# dsp.net
KiCad netlist of a schematic drawn in Altium Designer
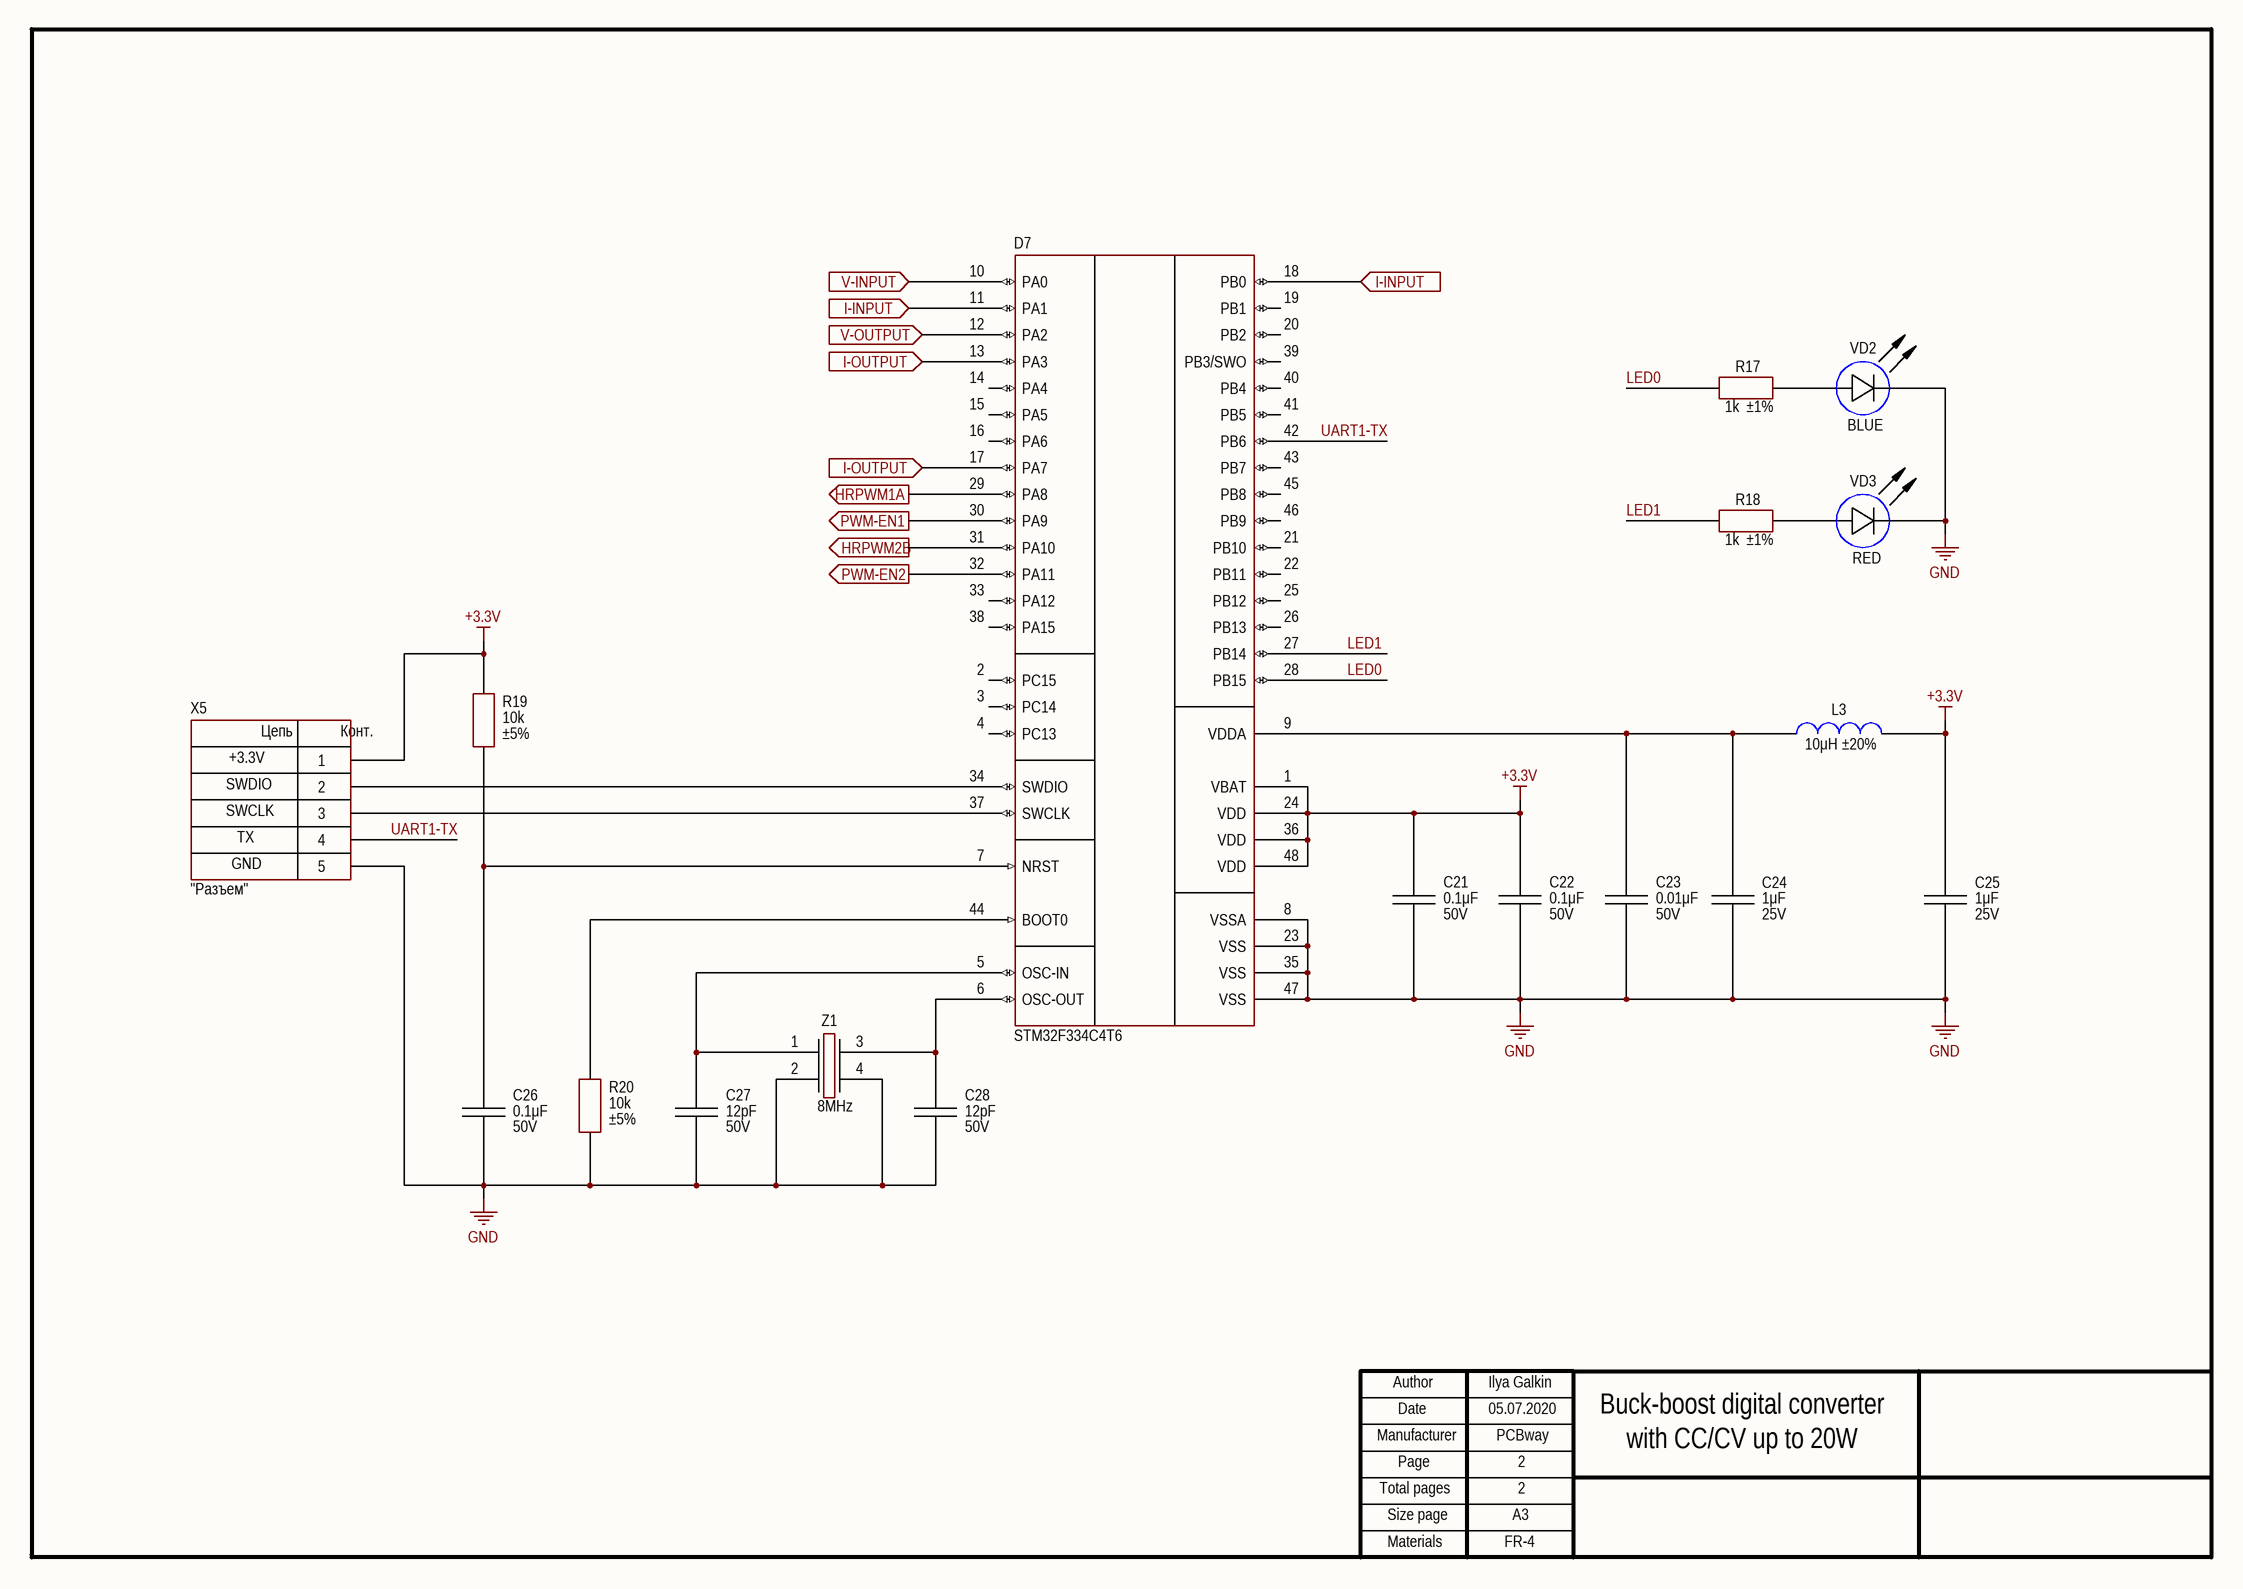
[diagram p0: dsp.SchDoc]

(export (version "E")
  (design (tool "Eeschema 10.0.6"))
  (components
    (comp (ref "C21")
      (value "0.1μF")
      (footprint "CAP: 0603")
      (fields
        (field (name "MANUFACTURER") "Yageo")
        (field (name "PARTNUMBER") "CL10B104KB8WPND")
        (field (name "VALUEMANUFACTURERPARTNUMBER") "Ceramic capacitor, 0.1μF, X7R, ±10%, 50V, 0603, -55...+125°C")
        (field (name "VOLTAGE") "50V")
      )
      (libsource (lib "Capacitor") (part "Ceramic_0603"))
    )
    (comp (ref "C22")
      (value "0.1μF")
      (footprint "CAP: 0603")
      (fields
        (field (name "MANUFACTURER") "Yageo")
        (field (name "PARTNUMBER") "CL10B104KB8WPND")
        (field (name "VALUEMANUFACTURERPARTNUMBER") "Ceramic capacitor, 0.1μF, X7R, ±10%, 50V, 0603, -55...+125°C")
        (field (name "VOLTAGE") "50V")
      )
      (libsource (lib "Capacitor") (part "Ceramic_0603"))
    )
    (comp (ref "C23")
      (value "0.01μF")
      (footprint "CAP: 0603")
      (fields
        (field (name "MANUFACTURER") "Yageo")
        (field (name "PARTNUMBER") "CL10B103KB8NNNC")
        (field (name "VALUEMANUFACTURERPARTNUMBER") "Ceramic capacitor, 0.01μF, X7R, ±10%, 50V, 0603, -55...+125°C")
        (field (name "VOLTAGE") "50V")
      )
      (libsource (lib "Capacitor") (part "Ceramic_0603"))
    )
    (comp (ref "C24")
      (value "1μF")
      (footprint "CAP: 0603")
      (fields
        (field (name "MANUFACTURER") "Samsung")
        (field (name "PARTNUMBER") "CL10B105KA8NNNC")
        (field (name "VALUEMANUFACTURERPARTNUMBER") "Ceramic capacitor, 1μF, X7R, ±10%, 25V, 0603, -55...+125°C")
        (field (name "VOLTAGE") "25V")
      )
      (libsource (lib "Capacitor") (part "Ceramic_0603"))
    )
    (comp (ref "C25")
      (value "1μF")
      (footprint "CAP: 0603")
      (fields
        (field (name "MANUFACTURER") "Samsung")
        (field (name "PARTNUMBER") "CL10B105KA8NNNC")
        (field (name "VALUEMANUFACTURERPARTNUMBER") "Ceramic capacitor, 1μF, X7R, ±10%, 25V, 0603, -55...+125°C")
        (field (name "VOLTAGE") "25V")
      )
      (libsource (lib "Capacitor") (part "Ceramic_0603"))
    )
    (comp (ref "C26")
      (value "0.1μF")
      (footprint "CAP: 0603")
      (fields
        (field (name "MANUFACTURER") "Yageo")
        (field (name "PARTNUMBER") "CL10B104KB8WPND")
        (field (name "VALUEMANUFACTURERPARTNUMBER") "Ceramic capacitor, 0.1μF, X7R, ±10%, 50V, 0603, -55...+125°C")
        (field (name "VOLTAGE") "50V")
      )
      (libsource (lib "Capacitor") (part "Ceramic_0603"))
    )
    (comp (ref "C27")
      (value "12pF")
      (footprint "CAP: 0603")
      (fields
        (field (name "MANUFACTURER") "Samsung")
        (field (name "PARTNUMBER") "CL10C120JB8NNNC")
        (field (name "VALUEMANUFACTURERPARTNUMBER") "Ceramic capacitor, 12pF, NPO, ±10%, 50V, 0603, -55...+125°C")
        (field (name "VOLTAGE") "50V")
      )
      (libsource (lib "Capacitor") (part "Ceramic_0603"))
    )
    (comp (ref "C28")
      (value "12pF")
      (footprint "CAP: 0603")
      (fields
        (field (name "MANUFACTURER") "Samsung")
        (field (name "PARTNUMBER") "CL10C120JB8NNNC")
        (field (name "VALUEMANUFACTURERPARTNUMBER") "Ceramic capacitor, 12pF, NPO, ±10%, 50V, 0603, -55...+125°C")
        (field (name "VOLTAGE") "50V")
      )
      (libsource (lib "Capacitor") (part "Ceramic_0603"))
    )
    (comp (ref "D7")
      (value "~")
      (footprint "48-LQFP")
      (description "Cortex-M4")
      (fields
        (field (name "MANUFACTURER") "STMicroelectronics")
        (field (name "VALUEMANUFACTURERPARTNUMBER") "IC microcontroller, 32-Bit, Cortex-M4, 72MHz, 16KB, 12KB, 2...3.6V, -40...+85°C, 48-LQFP")
        (field (name "PARTNUMBER") "STM32F334C4T6")
      )
      (libsource (lib "IC. MCU") (part "STM32F334C4T6"))
    )
    (comp (ref "L3")
      (value "10μH")
      (footprint "IND: 0603")
      (fields
        (field (name "MANUFACTURER") "Murata Electronics")
        (field (name "PARTNUMBER") "LQM18FN100M00D")
        (field (name "VALUEMANUFACTURERPARTNUMBER") "Fixed inductor, 10μH, ±20%, 0603, 50mA, -55...+125°C")
        (field (name "TOLERANCE") "±20%")
      )
      (libsource (lib "Inductor") (part "Inductor_0603"))
    )
    (comp (ref "R17")
      (value "1k")
      (footprint "RES: 0603")
      (fields
        (field (name "MANUFACTURER") "Yageo")
        (field (name "PARTNUMBER") "RC0603FR-071KL")
        (field (name "VALUEMANUFACTURERPARTNUMBER") "Resistor film, 1k, ±1%, 0603, 0.1W, -55...+125°C")
        (field (name "TOLERANCE") "±1%")
      )
      (libsource (lib "Resistor") (part "Resistor_0603"))
    )
    (comp (ref "R18")
      (value "1k")
      (footprint "RES: 0603")
      (fields
        (field (name "MANUFACTURER") "Yageo")
        (field (name "PARTNUMBER") "RC0603FR-071KL")
        (field (name "VALUEMANUFACTURERPARTNUMBER") "Resistor film, 1k, ±1%, 0603, 0.1W, -55...+125°C")
        (field (name "TOLERANCE") "±1%")
      )
      (libsource (lib "Resistor") (part "Resistor_0603"))
    )
    (comp (ref "R19")
      (value "10k")
      (footprint "RES: 0603")
      (fields
        (field (name "MANUFACTURER") "Yageo")
        (field (name "PARTNUMBER") "RC0603JR-0710KL")
        (field (name "VALUEMANUFACTURERPARTNUMBER") "Resistor film, 10k, ±5%, 0603, 0.1W, -55...+125°C")
        (field (name "TOLERANCE") "±5%")
      )
      (libsource (lib "") (part "Resistor_0603_1"))
    )
    (comp (ref "R20")
      (value "10k")
      (footprint "RES: 0603")
      (fields
        (field (name "MANUFACTURER") "Yageo")
        (field (name "PARTNUMBER") "RC0603JR-0710KL")
        (field (name "VALUEMANUFACTURERPARTNUMBER") "Resistor film, 10k, ±5%, 0603, 0.1W, -55...+125°C")
        (field (name "TOLERANCE") "±5%")
      )
      (libsource (lib "") (part "Resistor_0603_1"))
    )
    (comp (ref "VD2")
      (value "~")
      (footprint "LED: 0603B")
      (fields
        (field (name "MANUFACTURER") "Wurth")
        (field (name "VALUEMANUFACTURERPARTNUMBER") "LED, 20mA, 3.2V, 0603, -55...+150°C")
        (field (name "PARTNUMBER") "150060BS75000")
        (field (name "COLOR") "BLUE")
      )
      (libsource (lib "Diode") (part "LED_single"))
    )
    (comp (ref "VD3")
      (value "~")
      (footprint "LED: 0603R")
      (fields
        (field (name "MANUFACTURER") "Wurth")
        (field (name "VALUEMANUFACTURERPARTNUMBER") "LED, 20 mA, 2V, 0603, -55...+150°C")
        (field (name "PARTNUMBER") "150060RS75000")
        (field (name "COLOR") "RED")
      )
      (libsource (lib "Diode") (part "LED_single"))
    )
    (comp (ref "X5")
      (value "~")
      (footprint "CON: SM05B-GHS")
      (fields
        (field (name "MANUFACTURER") "JST")
        (field (name "VALUEMANUFACTURERPARTNUMBER") "Connector, 5pin, 1.25mm, 50VDC, 1A")
        (field (name "PARTNUMBER") "SM05B-GHS")
        (field (name "COMMENTTEXT") "\"Разъем\"")
      )
      (libsource (lib "Connector") (part "Connector_SM05B"))
    )
    (comp (ref "Z1")
      (value "~")
      (footprint "OSC: 3225")
      (fields
        (field (name "MANUFACTURER") "ECS")
        (field (name "PARTNUMBER") "ECS-80-12-33-JGN-TR")
        (field (name "VALUEMANUFACTURERPARTNUMBER") "Crystal, 8MHz, 12pF, ±30ppm, case 3225, -40...+85°C")
        (field (name "FREQUENCY") "8MHz")
      )
      (libsource (lib "Oscilator") (part "Crystal_3225"))
    )
  )
  (nets
    (net (code "1") (name "+3.3V") (class "Default")
      (node (ref "C21") (pin "2") (pinfunction "2_2") (pintype "power_in"))
      (node (ref "C22") (pin "2") (pinfunction "2_2") (pintype "power_in"))
      (node (ref "C25") (pin "2") (pinfunction "2_2") (pintype "power_in"))
      (node (ref "D7") (pin "1") (pinfunction "VBAT_1") (pintype "passive"))
      (node (ref "D7") (pin "24") (pinfunction "VDD_24") (pintype "passive"))
      (node (ref "D7") (pin "36") (pinfunction "VDD_36") (pintype "passive"))
      (node (ref "D7") (pin "48") (pinfunction "VDD_48") (pintype "passive"))
      (node (ref "L3") (pin "1") (pinfunction "1_1") (pintype "passive"))
      (node (ref "R19") (pin "2") (pinfunction "2_2") (pintype "passive"))
      (node (ref "X5") (pin "1") (pinfunction "1_1") (pintype "passive"))
    )
    (net (code "2") (name "/HRPWM1A") (class "Default")
      (node (ref "D7") (pin "29") (pinfunction "PA8_29") (pintype "bidirectional"))
    )
    (net (code "3") (name "/HRPWM2B") (class "Default")
      (node (ref "D7") (pin "31") (pinfunction "PA10_31") (pintype "bidirectional"))
    )
    (net (code "4") (name "/I-INPUT") (class "Default")
      (node (ref "D7") (pin "11") (pinfunction "PA1_11") (pintype "bidirectional"))
      (node (ref "D7") (pin "18") (pinfunction "PB0_18") (pintype "bidirectional"))
    )
    (net (code "5") (name "/I-OUTPUT") (class "Default")
      (node (ref "D7") (pin "13") (pinfunction "PA3_13") (pintype "bidirectional"))
      (node (ref "D7") (pin "17") (pinfunction "PA7_17") (pintype "bidirectional"))
    )
    (net (code "6") (name "/LED0") (class "Default")
      (node (ref "D7") (pin "28") (pinfunction "PB15_28") (pintype "bidirectional"))
      (node (ref "R17") (pin "2") (pinfunction "2_2") (pintype "passive"))
    )
    (net (code "7") (name "/LED1") (class "Default")
      (node (ref "D7") (pin "27") (pinfunction "PB14_27") (pintype "bidirectional"))
      (node (ref "R18") (pin "2") (pinfunction "2_2") (pintype "passive"))
    )
    (net (code "8") (name "/PWM-EN1") (class "Default")
      (node (ref "D7") (pin "30") (pinfunction "PA9_30") (pintype "bidirectional"))
    )
    (net (code "9") (name "/PWM-EN2") (class "Default")
      (node (ref "D7") (pin "32") (pinfunction "PA11_32") (pintype "bidirectional"))
    )
    (net (code "10") (name "/UART1-TX") (class "Default")
      (node (ref "D7") (pin "42") (pinfunction "PB6_42") (pintype "bidirectional"))
      (node (ref "X5") (pin "4") (pinfunction "4_4") (pintype "power_in"))
    )
    (net (code "11") (name "/V-INPUT") (class "Default")
      (node (ref "D7") (pin "10") (pinfunction "PA0_10") (pintype "bidirectional"))
    )
    (net (code "12") (name "/V-OUTPUT") (class "Default")
      (node (ref "D7") (pin "12") (pinfunction "PA2_12") (pintype "bidirectional"))
    )
    (net (code "13") (name "GND") (class "Default")
      (node (ref "C21") (pin "1") (pinfunction "1_1") (pintype "power_in"))
      (node (ref "C22") (pin "1") (pinfunction "1_1") (pintype "power_in"))
      (node (ref "C23") (pin "1") (pinfunction "1_1") (pintype "power_in"))
      (node (ref "C24") (pin "1") (pinfunction "1_1") (pintype "power_in"))
      (node (ref "C25") (pin "1") (pinfunction "1_1") (pintype "power_in"))
      (node (ref "C26") (pin "1") (pinfunction "1_1") (pintype "power_in"))
      (node (ref "C27") (pin "1") (pinfunction "1_1") (pintype "power_in"))
      (node (ref "C28") (pin "1") (pinfunction "1_1") (pintype "power_in"))
      (node (ref "D7") (pin "23") (pinfunction "VSS_23") (pintype "passive"))
      (node (ref "D7") (pin "35") (pinfunction "VSS_35") (pintype "passive"))
      (node (ref "D7") (pin "47") (pinfunction "VSS_47") (pintype "passive"))
      (node (ref "D7") (pin "8") (pinfunction "VSSA_8") (pintype "passive"))
      (node (ref "R20") (pin "1") (pinfunction "1_1") (pintype "passive"))
      (node (ref "VD2") (pin "2") (pinfunction "C_2") (pintype "passive"))
      (node (ref "VD3") (pin "2") (pinfunction "C_2") (pintype "passive"))
      (node (ref "X5") (pin "5") (pinfunction "5_5") (pintype "power_in"))
      (node (ref "Z1") (pin "2") (pinfunction "2_2") (pintype "passive"))
      (node (ref "Z1") (pin "4") (pinfunction "4_4") (pintype "passive"))
    )
    (net (code "14") (name "Net-(D7-BOOT0)") (class "Default")
      (node (ref "D7") (pin "44") (pinfunction "BOOT0_44") (pintype "input"))
      (node (ref "R20") (pin "2") (pinfunction "2_2") (pintype "passive"))
    )
    (net (code "15") (name "Net-(D7-NRST)") (class "Default")
      (node (ref "C26") (pin "2") (pinfunction "2_2") (pintype "power_in"))
      (node (ref "D7") (pin "7") (pinfunction "NRST_7") (pintype "input"))
      (node (ref "R19") (pin "1") (pinfunction "1_1") (pintype "passive"))
    )
    (net (code "16") (name "Net-(D7-OSC-IN)") (class "Default")
      (node (ref "C27") (pin "2") (pinfunction "2_2") (pintype "power_in"))
      (node (ref "D7") (pin "5") (pinfunction "OSC-IN_5") (pintype "bidirectional"))
      (node (ref "Z1") (pin "1") (pinfunction "1_1") (pintype "passive"))
    )
    (net (code "17") (name "Net-(D7-OSC-OUT)") (class "Default")
      (node (ref "C28") (pin "2") (pinfunction "2_2") (pintype "power_in"))
      (node (ref "D7") (pin "6") (pinfunction "OSC-OUT_6") (pintype "bidirectional"))
      (node (ref "Z1") (pin "3") (pinfunction "3_3") (pintype "passive"))
    )
    (net (code "18") (name "Net-(D7-SWCLK)") (class "Default")
      (node (ref "D7") (pin "37") (pinfunction "SWCLK_37") (pintype "bidirectional"))
      (node (ref "X5") (pin "3") (pinfunction "3_3") (pintype "power_in"))
    )
    (net (code "19") (name "Net-(D7-SWDIO)") (class "Default")
      (node (ref "D7") (pin "34") (pinfunction "SWDIO_34") (pintype "bidirectional"))
      (node (ref "X5") (pin "2") (pinfunction "2_2") (pintype "passive"))
    )
    (net (code "20") (name "Net-(D7-VDDA)") (class "Default")
      (node (ref "C23") (pin "2") (pinfunction "2_2") (pintype "power_in"))
      (node (ref "C24") (pin "2") (pinfunction "2_2") (pintype "power_in"))
      (node (ref "D7") (pin "9") (pinfunction "VDDA_9") (pintype "passive"))
      (node (ref "L3") (pin "2") (pinfunction "2_2") (pintype "passive"))
    )
    (net (code "21") (name "Net-(VD2-A)") (class "Default")
      (node (ref "R17") (pin "1") (pinfunction "1_1") (pintype "passive"))
      (node (ref "VD2") (pin "1") (pinfunction "A_1") (pintype "passive"))
    )
    (net (code "22") (name "Net-(VD3-A)") (class "Default")
      (node (ref "R18") (pin "1") (pinfunction "1_1") (pintype "passive"))
      (node (ref "VD3") (pin "1") (pinfunction "A_1") (pintype "passive"))
    )
    (net (code "23") (name "unconnected-(D7-PA4-Pad14)") (class "Default")
      (node (ref "D7") (pin "14") (pinfunction "PA4_14") (pintype "bidirectional"))
    )
    (net (code "24") (name "unconnected-(D7-PA5-Pad15)") (class "Default")
      (node (ref "D7") (pin "15") (pinfunction "PA5_15") (pintype "bidirectional"))
    )
    (net (code "25") (name "unconnected-(D7-PA6-Pad16)") (class "Default")
      (node (ref "D7") (pin "16") (pinfunction "PA6_16") (pintype "bidirectional"))
    )
    (net (code "26") (name "unconnected-(D7-PA12-Pad33)") (class "Default")
      (node (ref "D7") (pin "33") (pinfunction "PA12_33") (pintype "bidirectional"))
    )
    (net (code "27") (name "unconnected-(D7-PA15-Pad38)") (class "Default")
      (node (ref "D7") (pin "38") (pinfunction "PA15_38") (pintype "bidirectional"))
    )
    (net (code "28") (name "unconnected-(D7-PB1-Pad19)") (class "Default")
      (node (ref "D7") (pin "19") (pinfunction "PB1_19") (pintype "bidirectional"))
    )
    (net (code "29") (name "unconnected-(D7-PB2-Pad20)") (class "Default")
      (node (ref "D7") (pin "20") (pinfunction "PB2_20") (pintype "bidirectional"))
    )
    (net (code "30") (name "unconnected-(D7-PB3{slash}SWO-Pad39)") (class "Default")
      (node (ref "D7") (pin "39") (pinfunction "PB3/SWO_39") (pintype "bidirectional"))
    )
    (net (code "31") (name "unconnected-(D7-PB4-Pad40)") (class "Default")
      (node (ref "D7") (pin "40") (pinfunction "PB4_40") (pintype "bidirectional"))
    )
    (net (code "32") (name "unconnected-(D7-PB5-Pad41)") (class "Default")
      (node (ref "D7") (pin "41") (pinfunction "PB5_41") (pintype "bidirectional"))
    )
    (net (code "33") (name "unconnected-(D7-PB7-Pad43)") (class "Default")
      (node (ref "D7") (pin "43") (pinfunction "PB7_43") (pintype "bidirectional"))
    )
    (net (code "34") (name "unconnected-(D7-PB8-Pad45)") (class "Default")
      (node (ref "D7") (pin "45") (pinfunction "PB8_45") (pintype "bidirectional"))
    )
    (net (code "35") (name "unconnected-(D7-PB9-Pad46)") (class "Default")
      (node (ref "D7") (pin "46") (pinfunction "PB9_46") (pintype "bidirectional"))
    )
    (net (code "36") (name "unconnected-(D7-PB10-Pad21)") (class "Default")
      (node (ref "D7") (pin "21") (pinfunction "PB10_21") (pintype "bidirectional"))
    )
    (net (code "37") (name "unconnected-(D7-PB11-Pad22)") (class "Default")
      (node (ref "D7") (pin "22") (pinfunction "PB11_22") (pintype "bidirectional"))
    )
    (net (code "38") (name "unconnected-(D7-PB12-Pad25)") (class "Default")
      (node (ref "D7") (pin "25") (pinfunction "PB12_25") (pintype "bidirectional"))
    )
    (net (code "39") (name "unconnected-(D7-PB13-Pad26)") (class "Default")
      (node (ref "D7") (pin "26") (pinfunction "PB13_26") (pintype "bidirectional"))
    )
    (net (code "40") (name "unconnected-(D7-PC13-Pad4)") (class "Default")
      (node (ref "D7") (pin "4") (pinfunction "PC13_4") (pintype "bidirectional"))
    )
    (net (code "41") (name "unconnected-(D7-PC14-Pad3)") (class "Default")
      (node (ref "D7") (pin "3") (pinfunction "PC14_3") (pintype "bidirectional"))
    )
    (net (code "42") (name "unconnected-(D7-PC15-Pad2)") (class "Default")
      (node (ref "D7") (pin "2") (pinfunction "PC15_2") (pintype "bidirectional"))
    )
  )
)
